# DE-160516.net
KiCad netlist of a schematic drawn in Altium Designer
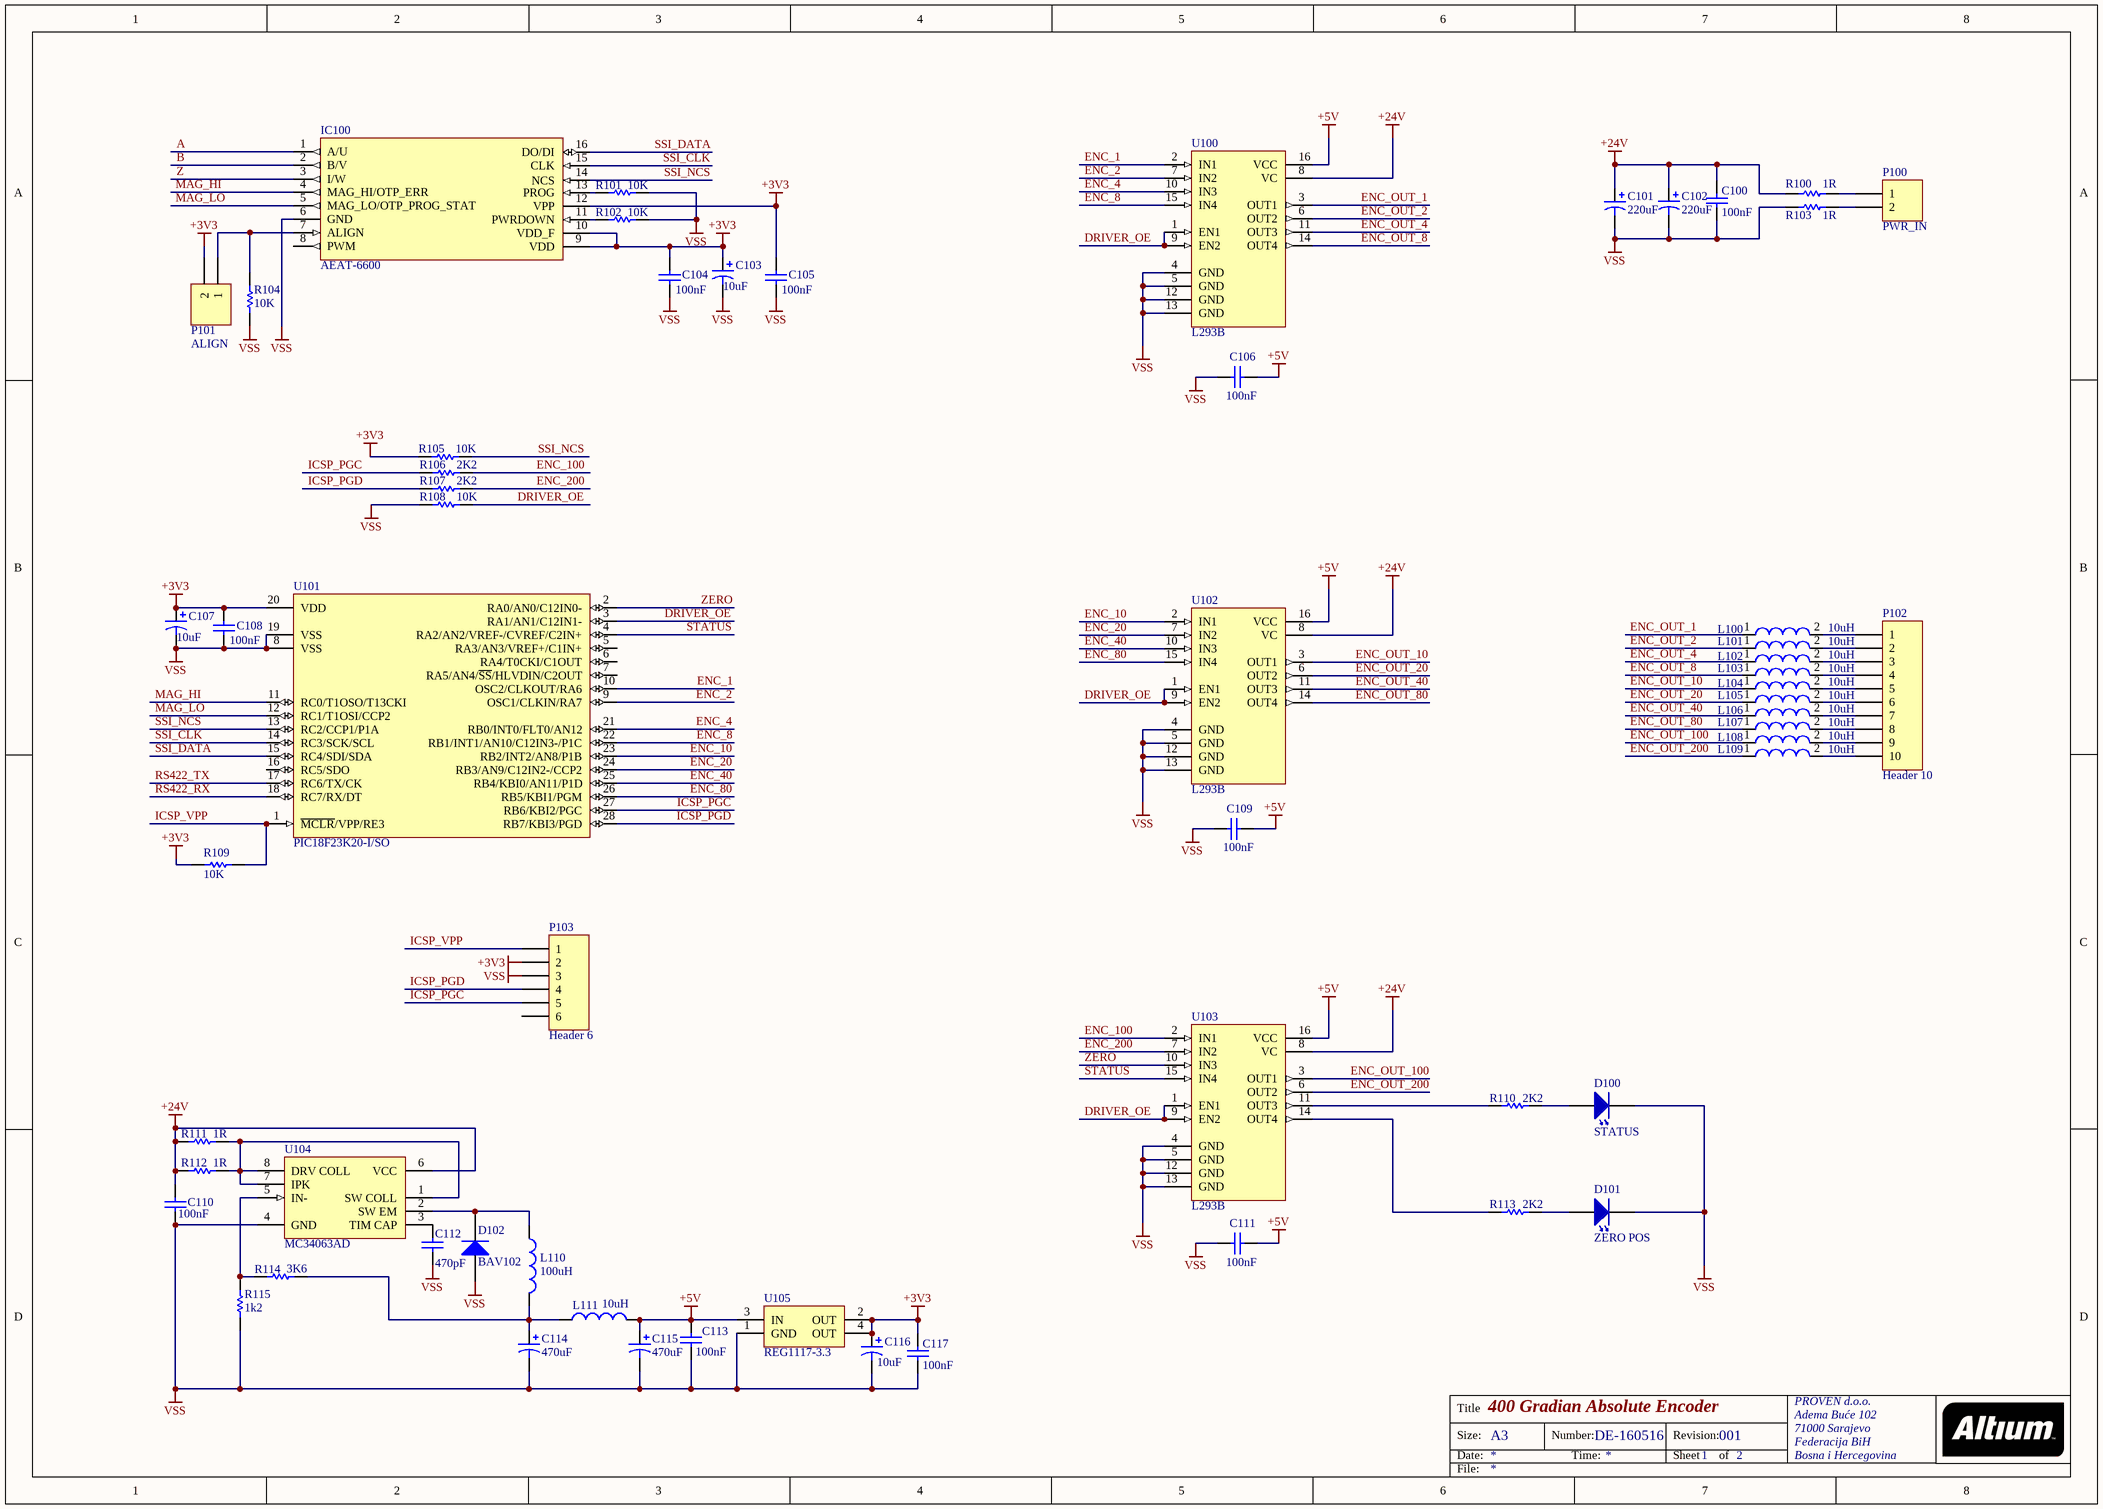
[diagram p0: DE-160516.SchDoc]

(export (version "E")
  (design (tool "Eeschema 10.0.6"))
  (components
    (comp (ref "C100")
      (value "100nF")
      (footprint "0805")
      (description "Ceramic Chip Capacitor - Standard")
      (fields (field (name "PUBLISHER") "Altium Limited"))
      (libsource (lib "KEMET Chip Capacitor") (part "C0805"))
    )
    (comp (ref "C101")
      (value "220uF")
      (footprint "E")
      (description "Solid Aluminum Capacitor with Organic Semiconductor Electrolyte: 100uF, 20V, Bulk Pack")
      (fields (field (name "PUBLISHER") "Altium Limited"))
      (libsource (lib "Vishay Electrolytic Radial-Lead Capacitor") (part "94SS107X0020EBP"))
    )
    (comp (ref "C102")
      (value "220uF")
      (footprint "E")
      (description "Solid Aluminum Capacitor with Organic Semiconductor Electrolyte: 100uF, 20V, Bulk Pack")
      (fields (field (name "PUBLISHER") "Altium Limited"))
      (libsource (lib "Vishay Electrolytic Radial-Lead Capacitor") (part "94SS107X0020EBP"))
    )
    (comp (ref "C103")
      (value "10uF")
      (footprint "C")
      (description "Solid Aluminum Capacitor with Organic Semiconductor Electrolyte: 10uF, 16V, Bulk Pack")
      (fields (field (name "PUBLISHER") "Altium Limited"))
      (libsource (lib "Vishay Electrolytic Radial-Lead Capacitor") (part "94SC106X0016CBP"))
    )
    (comp (ref "C104")
      (value "100nF")
      (footprint "0805")
      (description "Ceramic Chip Capacitor - Standard")
      (fields (field (name "PUBLISHER") "Altium Limited"))
      (libsource (lib "KEMET Chip Capacitor") (part "C0805"))
    )
    (comp (ref "C105")
      (value "100nF")
      (footprint "0805")
      (description "Ceramic Chip Capacitor - Standard")
      (fields (field (name "PUBLISHER") "Altium Limited"))
      (libsource (lib "KEMET Chip Capacitor") (part "C0805"))
    )
    (comp (ref "C106")
      (value "100nF")
      (footprint "0805")
      (description "Ceramic Chip Capacitor - Standard")
      (fields (field (name "PUBLISHER") "Altium Limited"))
      (libsource (lib "KEMET Chip Capacitor") (part "C0805"))
    )
    (comp (ref "C107")
      (value "10uF")
      (footprint "C")
      (description "Solid Aluminum Capacitor with Organic Semiconductor Electrolyte: 10uF, 16V, Bulk Pack")
      (fields (field (name "PUBLISHER") "Altium Limited"))
      (libsource (lib "Vishay Electrolytic Radial-Lead Capacitor") (part "94SC106X0016CBP"))
    )
    (comp (ref "C108")
      (value "100nF")
      (footprint "0805")
      (description "Ceramic Chip Capacitor - Standard")
      (fields (field (name "PUBLISHER") "Altium Limited"))
      (libsource (lib "KEMET Chip Capacitor") (part "C0805"))
    )
    (comp (ref "C109")
      (value "100nF")
      (footprint "0805")
      (description "Ceramic Chip Capacitor - Standard")
      (fields (field (name "PUBLISHER") "Altium Limited"))
      (libsource (lib "KEMET Chip Capacitor") (part "C0805"))
    )
    (comp (ref "C110")
      (value "100nF")
      (footprint "1206")
      (description "Ceramic Chip Capacitor - Standard")
      (fields (field (name "PUBLISHER") "Altium Limited"))
      (libsource (lib "KEMET Chip Capacitor") (part "C1206"))
    )
    (comp (ref "C111")
      (value "100nF")
      (footprint "0805")
      (description "Ceramic Chip Capacitor - Standard")
      (fields (field (name "PUBLISHER") "Altium Limited"))
      (libsource (lib "KEMET Chip Capacitor") (part "C0805"))
    )
    (comp (ref "C112")
      (value "470pF")
      (footprint "0805")
      (description "Ceramic Chip Capacitor - Standard")
      (fields (field (name "PUBLISHER") "Altium Limited"))
      (libsource (lib "KEMET Chip Capacitor") (part "C0805"))
    )
    (comp (ref "C113")
      (value "100nF")
      (footprint "0805")
      (description "Ceramic Chip Capacitor - Standard")
      (fields (field (name "PUBLISHER") "Altium Limited"))
      (libsource (lib "KEMET Chip Capacitor") (part "C0805"))
    )
    (comp (ref "C114")
      (value "470uF")
      (footprint "CAPPR2.5-6.3X11")
      (description "Aluminum Electrolytic Capacitor, Radial Style with Long Leads: 470uF, 10V")
      (fields (field (name "PUBLISHER") "Altium Limited"))
      (libsource (lib "Vishay Roederstein Electrolytic Radial-Lead Capacitor") (part "EKA00BA347C00"))
    )
    (comp (ref "C115")
      (value "470uF")
      (footprint "CAPPR2.5-6.3X11")
      (description "Aluminum Electrolytic Capacitor, Radial Style with Long Leads: 470uF, 10V")
      (fields (field (name "PUBLISHER") "Altium Limited"))
      (libsource (lib "Vishay Roederstein Electrolytic Radial-Lead Capacitor") (part "EKA00BA347C00"))
    )
    (comp (ref "C116")
      (value "10uF")
      (footprint "49BC-C")
      (fields (field (name "PUBLISHER") "Altium Limited"))
      (libsource (lib "Vishay Sprague Tantalum Chip Capacitor") (part "49BC685B010M"))
    )
    (comp (ref "C117")
      (value "100nF")
      (footprint "0805")
      (description "Ceramic Chip Capacitor - Standard")
      (fields (field (name "PUBLISHER") "Altium Limited"))
      (libsource (lib "KEMET Chip Capacitor") (part "C0805"))
    )
    (comp (ref "D100")
      (value "STATUS")
      (footprint "LED 3mm")
      (description "LED dioda 3 mm")
      (libsource (lib "Schlib1") (part "LED 3mm yellow"))
    )
    (comp (ref "D101")
      (value "ZERO POS")
      (footprint "LED 3mm")
      (description "LED dioda 3 mm")
      (libsource (lib "Schlib1") (part "LED 3mm yellow"))
    )
    (comp (ref "D102")
      (value "BAV102")
      (footprint "SOD80C")
      (description "General-purpose Diode")
      (fields (field (name "PUBLISHER") "Altium Limited"))
      (libsource (lib "Philips Discrete Diode - Switching") (part "BAV102"))
    )
    (comp (ref "IC100")
      (value "AEAT-6600")
      (footprint "TSSOP16")
      (description "Absolute encoder IC")
      (libsource (lib "ABS_ENC") (part "AEAT-6600"))
    )
    (comp (ref "L100")
      (value "10uH")
      (footprint "SMD-0603")
      (description "SMD-Multilayer Inductor WE-MI, L = 0.10µH")
      (libsource (lib "Wuerth Elektronik Filter Inductor") (part "7447962"))
    )
    (comp (ref "L101")
      (value "10uH")
      (footprint "SMD-0603")
      (description "SMD-Multilayer Inductor WE-MI, L = 0.10µH")
      (libsource (lib "Wuerth Elektronik Filter Inductor") (part "7447962"))
    )
    (comp (ref "L102")
      (value "10uH")
      (footprint "SMD-0603")
      (description "SMD-Multilayer Inductor WE-MI, L = 0.10µH")
      (libsource (lib "Wuerth Elektronik Filter Inductor") (part "7447962"))
    )
    (comp (ref "L103")
      (value "10uH")
      (footprint "SMD-0603")
      (description "SMD-Multilayer Inductor WE-MI, L = 0.10µH")
      (libsource (lib "Wuerth Elektronik Filter Inductor") (part "7447962"))
    )
    (comp (ref "L104")
      (value "10uH")
      (footprint "SMD-0603")
      (description "SMD-Multilayer Inductor WE-MI, L = 0.10µH")
      (libsource (lib "Wuerth Elektronik Filter Inductor") (part "7447962"))
    )
    (comp (ref "L105")
      (value "10uH")
      (footprint "SMD-0603")
      (description "SMD-Multilayer Inductor WE-MI, L = 0.10µH")
      (libsource (lib "Wuerth Elektronik Filter Inductor") (part "7447962"))
    )
    (comp (ref "L106")
      (value "10uH")
      (footprint "SMD-0603")
      (description "SMD-Multilayer Inductor WE-MI, L = 0.10µH")
      (libsource (lib "Wuerth Elektronik Filter Inductor") (part "7447962"))
    )
    (comp (ref "L107")
      (value "10uH")
      (footprint "SMD-0603")
      (description "SMD-Multilayer Inductor WE-MI, L = 0.10µH")
      (libsource (lib "Wuerth Elektronik Filter Inductor") (part "7447962"))
    )
    (comp (ref "L108")
      (value "10uH")
      (footprint "SMD-0603")
      (description "SMD-Multilayer Inductor WE-MI, L = 0.10µH")
      (libsource (lib "Wuerth Elektronik Filter Inductor") (part "7447962"))
    )
    (comp (ref "L109")
      (value "10uH")
      (footprint "SMD-0603")
      (description "SMD-Multilayer Inductor WE-MI, L = 0.10µH")
      (libsource (lib "Wuerth Elektronik Filter Inductor") (part "7447962"))
    )
    (comp (ref "L110")
      (value "100uH")
      (footprint "Miscellaneous Devices:RB5-10.5")
      (description "SMT Power Choke Coil; Size 7.3×6.6×3.0mm, ±20% Tolerance, 0.82uH, 13A")
      (fields (field (name "PUBLISHER") "Altium Limited"))
      (libsource (lib "SSM Inductor") (part "PCMC063T-R82MN"))
    )
    (comp (ref "L111")
      (value "10uH")
      (footprint "Miscellaneous Devices:RB5-10.5")
      (description "SMT Power Choke Coil; Size 7.3×6.6×3.0mm, ±20% Tolerance, 0.82uH, 13A")
      (fields (field (name "PUBLISHER") "Altium Limited"))
      (libsource (lib "SSM Inductor") (part "PCMC063T-R82MN"))
    )
    (comp (ref "P100")
      (value "PWR_IN")
      (footprint "HDR1X2")
      (description "Header, 2-Pin")
      (fields (field (name "PUBLISHER") "Altium Limited"))
      (libsource (lib "Miscellaneous Connectors") (part "Header 2"))
    )
    (comp (ref "P101")
      (value "ALIGN")
      (footprint "HDR1X2")
      (description "Header, 2-Pin")
      (fields (field (name "PUBLISHER") "Altium Limited"))
      (libsource (lib "") (part "Header 2_1"))
    )
    (comp (ref "P102")
      (value "Header 10")
      (footprint "HDR1X10")
      (description "Header, 10-Pin")
      (fields (field (name "PUBLISHER") "Altium Limited"))
      (libsource (lib "Miscellaneous Connectors") (part "Header 10"))
    )
    (comp (ref "P103")
      (value "Header 6")
      (footprint "HDR1X6")
      (description "Header, 6-Pin")
      (fields (field (name "PUBLISHER") "Altium Limited"))
      (libsource (lib "Miscellaneous Connectors") (part "Header 6"))
    )
    (comp (ref "R100")
      (value "1R")
      (footprint "RD6.35x2.3")
      (fields (field (name "PUBLISHER") "Altium Limited"))
      (libsource (lib "Panasonic Resistor") (part "ERD2FC"))
    )
    (comp (ref "R101")
      (value "10K")
      (footprint "ERA-0603")
      (fields (field (name "PUBLISHER") "Altium Limited"))
      (libsource (lib "Panasonic Resistor") (part "ERAV"))
    )
    (comp (ref "R102")
      (value "10K")
      (footprint "ERA-0603")
      (fields (field (name "PUBLISHER") "Altium Limited"))
      (libsource (lib "Panasonic Resistor") (part "ERAV"))
    )
    (comp (ref "R103")
      (value "1R")
      (footprint "RD6.35x2.3")
      (fields (field (name "PUBLISHER") "Altium Limited"))
      (libsource (lib "Panasonic Resistor") (part "ERD2FC"))
    )
    (comp (ref "R104")
      (value "10K")
      (footprint "ERA-0603")
      (fields (field (name "PUBLISHER") "Altium Limited"))
      (libsource (lib "Panasonic Resistor") (part "ERAV"))
    )
    (comp (ref "R105")
      (value "10K")
      (footprint "ERA-0603")
      (fields (field (name "PUBLISHER") "Altium Limited"))
      (libsource (lib "Panasonic Resistor") (part "ERAV"))
    )
    (comp (ref "R106")
      (value "2K2")
      (footprint "ERA-0603")
      (fields (field (name "PUBLISHER") "Altium Limited"))
      (libsource (lib "Panasonic Resistor") (part "ERAV"))
    )
    (comp (ref "R107")
      (value "2K2")
      (footprint "ERA-0603")
      (fields (field (name "PUBLISHER") "Altium Limited"))
      (libsource (lib "Panasonic Resistor") (part "ERAV"))
    )
    (comp (ref "R108")
      (value "10K")
      (footprint "ERA-0603")
      (fields (field (name "PUBLISHER") "Altium Limited"))
      (libsource (lib "Panasonic Resistor") (part "ERAV"))
    )
    (comp (ref "R109")
      (value "10K")
      (footprint "ERA-0603")
      (fields (field (name "PUBLISHER") "Altium Limited"))
      (libsource (lib "Panasonic Resistor") (part "ERAV"))
    )
    (comp (ref "R110")
      (value "2K2")
      (footprint "ERA-0603")
      (fields (field (name "PUBLISHER") "Altium Limited"))
      (libsource (lib "Panasonic Resistor") (part "ERAV"))
    )
    (comp (ref "R111")
      (value "1R")
      (footprint "ERA-0805")
      (fields (field (name "PUBLISHER") "Altium Limited"))
      (libsource (lib "Panasonic Resistor") (part "ERAS"))
    )
    (comp (ref "R112")
      (value "1R")
      (footprint "ERA-0805")
      (fields (field (name "PUBLISHER") "Altium Limited"))
      (libsource (lib "Panasonic Resistor") (part "ERAS"))
    )
    (comp (ref "R113")
      (value "2K2")
      (footprint "ERA-0603")
      (fields (field (name "PUBLISHER") "Altium Limited"))
      (libsource (lib "Panasonic Resistor") (part "ERAV"))
    )
    (comp (ref "R114")
      (value "3K6")
      (footprint "ERA-0805")
      (fields (field (name "PUBLISHER") "Altium Limited"))
      (libsource (lib "Panasonic Resistor") (part "ERAS"))
    )
    (comp (ref "R115")
      (value "1k2")
      (footprint "ERA-0805")
      (fields (field (name "PUBLISHER") "Altium Limited"))
      (libsource (lib "Panasonic Resistor") (part "ERAS"))
    )
    (comp (ref "U100")
      (value "L293B")
      (footprint "DIP16")
      (description "Push-Pull Four Channel Drivers")
      (fields (field (name "PUBLISHER") "Altium Limited"))
      (libsource (lib "ST Interface DC & Stepper Motor Controller") (part "L293B"))
    )
    (comp (ref "U101")
      (value "PIC18F23K20-I/SO")
      (footprint "SOIC-SO28_N")
      (description "Flash Microcontroller with nanoWatt XLP Technology, 28-pin SOIC, Industrial Temperature")
      (fields (field (name "PUBLISHER") "Altium Limited"))
      (libsource (lib "Microchip Microcontroller 8-Bit PIC18") (part "PIC18F23K20-I/SO"))
    )
    (comp (ref "U102")
      (value "L293B")
      (footprint "DIP16")
      (description "Push-Pull Four Channel Drivers")
      (fields (field (name "PUBLISHER") "Altium Limited"))
      (libsource (lib "ST Interface DC & Stepper Motor Controller") (part "L293B"))
    )
    (comp (ref "U103")
      (value "L293B")
      (footprint "DIP16")
      (description "Push-Pull Four Channel Drivers")
      (fields (field (name "PUBLISHER") "Altium Limited"))
      (libsource (lib "ST Interface DC & Stepper Motor Controller") (part "L293B"))
    )
    (comp (ref "U104")
      (value "MC34063AD")
      (footprint "751-05_N")
      (description "DC-to-DC Converter Control Circuit")
      (fields (field (name "PUBLISHER") "Altium Limited"))
      (libsource (lib "ON Semi Power Mgt DC-DC Converter") (part "MC34063AD"))
    )
    (comp (ref "U105")
      (value "REG1117-3.3")
      (footprint "ZZ311")
      (description "800mA and 1A Low Dropout Positive Regulator 2.85V, 3.3V, 5V, and Adjustable")
      (fields (field (name "PUBLISHER") "Altium Limited"))
      (libsource (lib "BB Power Mgt Voltage Regulator") (part "REG1117-3.3"))
    )
  )
  (nets
    (net (code "1") (name "+3V3") (class "Default")
      (node (ref "C103") (pin "1") (pinfunction "1_1") (pintype "passive"))
      (node (ref "C104") (pin "2") (pinfunction "2_2") (pintype "passive"))
      (node (ref "C105") (pin "2") (pinfunction "2_2") (pintype "passive"))
      (node (ref "C107") (pin "1") (pinfunction "1_1") (pintype "passive"))
      (node (ref "C108") (pin "2") (pinfunction "2_2") (pintype "passive"))
      (node (ref "C116") (pin "1") (pinfunction "1_1") (pintype "passive"))
      (node (ref "C117") (pin "2") (pinfunction "2_2") (pintype "passive"))
      (node (ref "IC100") (pin "10") (pinfunction "VDD_F_10") (pintype "power_in"))
      (node (ref "IC100") (pin "12") (pinfunction "VPP_12") (pintype "power_in"))
      (node (ref "IC100") (pin "9") (pinfunction "VDD_9") (pintype "power_in"))
      (node (ref "P101") (pin "2") (pinfunction "2_2") (pintype "passive"))
      (node (ref "P103") (pin "2") (pinfunction "2_2") (pintype "passive"))
      (node (ref "R105") (pin "2") (pinfunction "2_2") (pintype "passive"))
      (node (ref "R109") (pin "2") (pinfunction "2_2") (pintype "passive"))
      (node (ref "U101") (pin "20") (pinfunction "VDD_20") (pintype "power_in"))
      (node (ref "U105") (pin "2") (pinfunction "OUT_2") (pintype "power_in"))
      (node (ref "U105") (pin "4") (pinfunction "OUT_4") (pintype "power_in"))
    )
    (net (code "2") (name "+5V") (class "Default")
      (node (ref "C106") (pin "1") (pinfunction "1_1") (pintype "passive"))
      (node (ref "C109") (pin "1") (pinfunction "1_1") (pintype "passive"))
      (node (ref "C111") (pin "1") (pinfunction "1_1") (pintype "passive"))
      (node (ref "C113") (pin "2") (pinfunction "2_2") (pintype "passive"))
      (node (ref "C115") (pin "1") (pinfunction "1_1") (pintype "passive"))
      (node (ref "L111") (pin "2") (pinfunction "2_2") (pintype "passive"))
      (node (ref "U100") (pin "16") (pinfunction "VCC_16") (pintype "power_in"))
      (node (ref "U102") (pin "16") (pinfunction "VCC_16") (pintype "power_in"))
      (node (ref "U103") (pin "16") (pinfunction "VCC_16") (pintype "power_in"))
      (node (ref "U105") (pin "3") (pinfunction "IN_3") (pintype "power_in"))
    )
    (net (code "3") (name "+24V") (class "Default")
      (node (ref "C100") (pin "2") (pinfunction "2_2") (pintype "passive"))
      (node (ref "C101") (pin "1") (pinfunction "1_1") (pintype "passive"))
      (node (ref "C102") (pin "1") (pinfunction "1_1") (pintype "passive"))
      (node (ref "C110") (pin "2") (pinfunction "2_2") (pintype "passive"))
      (node (ref "R100") (pin "1") (pinfunction "1_1") (pintype "passive"))
      (node (ref "R111") (pin "1") (pinfunction "1_1") (pintype "passive"))
      (node (ref "R112") (pin "1") (pinfunction "1_1") (pintype "passive"))
      (node (ref "U100") (pin "8") (pinfunction "VC_8") (pintype "power_in"))
      (node (ref "U102") (pin "8") (pinfunction "VC_8") (pintype "power_in"))
      (node (ref "U103") (pin "8") (pinfunction "VC_8") (pintype "power_in"))
      (node (ref "U104") (pin "6") (pinfunction "VCC_6") (pintype "power_in"))
    )
    (net (code "4") (name "/A") (class "Default")
      (node (ref "IC100") (pin "1") (pinfunction "A/U_1") (pintype "output"))
    )
    (net (code "5") (name "/B") (class "Default")
      (node (ref "IC100") (pin "2") (pinfunction "B/V_2") (pintype "output"))
    )
    (net (code "6") (name "/DRIVER_OE") (class "Default")
      (node (ref "R108") (pin "1") (pinfunction "1_1") (pintype "passive"))
      (node (ref "U100") (pin "1") (pinfunction "EN1_1") (pintype "input"))
      (node (ref "U100") (pin "9") (pinfunction "EN2_9") (pintype "input"))
      (node (ref "U101") (pin "3") (pinfunction "RA1/AN1/C12IN1-_3") (pintype "bidirectional"))
      (node (ref "U102") (pin "1") (pinfunction "EN1_1") (pintype "input"))
      (node (ref "U102") (pin "9") (pinfunction "EN2_9") (pintype "input"))
      (node (ref "U103") (pin "1") (pinfunction "EN1_1") (pintype "input"))
      (node (ref "U103") (pin "9") (pinfunction "EN2_9") (pintype "input"))
    )
    (net (code "7") (name "/ENC_1") (class "Default")
      (node (ref "U100") (pin "2") (pinfunction "IN1_2") (pintype "input"))
      (node (ref "U101") (pin "10") (pinfunction "OSC2/CLKOUT/RA6_10") (pintype "bidirectional"))
    )
    (net (code "8") (name "/ENC_2") (class "Default")
      (node (ref "U100") (pin "7") (pinfunction "IN2_7") (pintype "input"))
      (node (ref "U101") (pin "9") (pinfunction "OSC1/CLKIN/RA7_9") (pintype "bidirectional"))
    )
    (net (code "9") (name "/ENC_4") (class "Default")
      (node (ref "U100") (pin "10") (pinfunction "IN3_10") (pintype "input"))
      (node (ref "U101") (pin "21") (pinfunction "RB0/INT0/FLT0/AN12_21") (pintype "bidirectional"))
    )
    (net (code "10") (name "/ENC_8") (class "Default")
      (node (ref "U100") (pin "15") (pinfunction "IN4_15") (pintype "input"))
      (node (ref "U101") (pin "22") (pinfunction "RB1/INT1/AN10/C12IN3-/P1C_22") (pintype "bidirectional"))
    )
    (net (code "11") (name "/ENC_10") (class "Default")
      (node (ref "U101") (pin "23") (pinfunction "RB2/INT2/AN8/P1B_23") (pintype "bidirectional"))
      (node (ref "U102") (pin "2") (pinfunction "IN1_2") (pintype "input"))
    )
    (net (code "12") (name "/ENC_20") (class "Default")
      (node (ref "U101") (pin "24") (pinfunction "RB3/AN9/C12IN2-/CCP2_24") (pintype "bidirectional"))
      (node (ref "U102") (pin "7") (pinfunction "IN2_7") (pintype "input"))
    )
    (net (code "13") (name "/ENC_40") (class "Default")
      (node (ref "U101") (pin "25") (pinfunction "RB4/KBI0/AN11/P1D_25") (pintype "bidirectional"))
      (node (ref "U102") (pin "10") (pinfunction "IN3_10") (pintype "input"))
    )
    (net (code "14") (name "/ENC_80") (class "Default")
      (node (ref "U101") (pin "26") (pinfunction "RB5/KBI1/PGM_26") (pintype "bidirectional"))
      (node (ref "U102") (pin "15") (pinfunction "IN4_15") (pintype "input"))
    )
    (net (code "15") (name "/ENC_100") (class "Default")
      (node (ref "R106") (pin "1") (pinfunction "1_1") (pintype "passive"))
      (node (ref "U103") (pin "2") (pinfunction "IN1_2") (pintype "input"))
    )
    (net (code "16") (name "/ENC_200") (class "Default")
      (node (ref "R107") (pin "1") (pinfunction "1_1") (pintype "passive"))
      (node (ref "U103") (pin "7") (pinfunction "IN2_7") (pintype "input"))
    )
    (net (code "17") (name "/ENC_OUT_1") (class "Default")
      (node (ref "L100") (pin "1") (pinfunction "1_1") (pintype "passive"))
      (node (ref "U100") (pin "3") (pinfunction "OUT1_3") (pintype "output"))
    )
    (net (code "18") (name "/ENC_OUT_2") (class "Default")
      (node (ref "L101") (pin "1") (pinfunction "1_1") (pintype "passive"))
      (node (ref "U100") (pin "6") (pinfunction "OUT2_6") (pintype "output"))
    )
    (net (code "19") (name "/ENC_OUT_4") (class "Default")
      (node (ref "L102") (pin "1") (pinfunction "1_1") (pintype "passive"))
      (node (ref "U100") (pin "11") (pinfunction "OUT3_11") (pintype "output"))
    )
    (net (code "20") (name "/ENC_OUT_8") (class "Default")
      (node (ref "L103") (pin "1") (pinfunction "1_1") (pintype "passive"))
      (node (ref "U100") (pin "14") (pinfunction "OUT4_14") (pintype "output"))
    )
    (net (code "21") (name "/ENC_OUT_10") (class "Default")
      (node (ref "L104") (pin "1") (pinfunction "1_1") (pintype "passive"))
      (node (ref "U102") (pin "3") (pinfunction "OUT1_3") (pintype "output"))
    )
    (net (code "22") (name "/ENC_OUT_20") (class "Default")
      (node (ref "L105") (pin "1") (pinfunction "1_1") (pintype "passive"))
      (node (ref "U102") (pin "6") (pinfunction "OUT2_6") (pintype "output"))
    )
    (net (code "23") (name "/ENC_OUT_40") (class "Default")
      (node (ref "L106") (pin "1") (pinfunction "1_1") (pintype "passive"))
      (node (ref "U102") (pin "11") (pinfunction "OUT3_11") (pintype "output"))
    )
    (net (code "24") (name "/ENC_OUT_80") (class "Default")
      (node (ref "L107") (pin "1") (pinfunction "1_1") (pintype "passive"))
      (node (ref "U102") (pin "14") (pinfunction "OUT4_14") (pintype "output"))
    )
    (net (code "25") (name "/ENC_OUT_100") (class "Default")
      (node (ref "L108") (pin "1") (pinfunction "1_1") (pintype "passive"))
      (node (ref "U103") (pin "3") (pinfunction "OUT1_3") (pintype "output"))
    )
    (net (code "26") (name "/ENC_OUT_200") (class "Default")
      (node (ref "L109") (pin "1") (pinfunction "1_1") (pintype "passive"))
      (node (ref "U103") (pin "6") (pinfunction "OUT2_6") (pintype "output"))
    )
    (net (code "27") (name "/ICSP_PGC") (class "Default")
      (node (ref "P103") (pin "5") (pinfunction "5_5") (pintype "passive"))
      (node (ref "R106") (pin "2") (pinfunction "2_2") (pintype "passive"))
      (node (ref "U101") (pin "27") (pinfunction "RB6/KBI2/PGC_27") (pintype "bidirectional"))
    )
    (net (code "28") (name "/ICSP_PGD") (class "Default")
      (node (ref "P103") (pin "4") (pinfunction "4_4") (pintype "passive"))
      (node (ref "R107") (pin "2") (pinfunction "2_2") (pintype "passive"))
      (node (ref "U101") (pin "28") (pinfunction "RB7/KBI3/PGD_28") (pintype "bidirectional"))
    )
    (net (code "29") (name "/ICSP_VPP") (class "Default")
      (node (ref "P103") (pin "1") (pinfunction "1_1") (pintype "passive"))
      (node (ref "R109") (pin "1") (pinfunction "1_1") (pintype "passive"))
      (node (ref "U101") (pin "1") (pinfunction "~{MCLR}/VPP/RE3_1") (pintype "input"))
    )
    (net (code "30") (name "/MAG_HI") (class "Default")
      (node (ref "IC100") (pin "4") (pinfunction "MAG_HI/OTP_ERR_4") (pintype "output"))
      (node (ref "U101") (pin "11") (pinfunction "RC0/T1OSO/T13CKI_11") (pintype "bidirectional"))
    )
    (net (code "31") (name "/MAG_LO") (class "Default")
      (node (ref "IC100") (pin "5") (pinfunction "MAG_LO/OTP_PROG_STAT_5") (pintype "output"))
      (node (ref "U101") (pin "12") (pinfunction "RC1/T1OSI/CCP2_12") (pintype "bidirectional"))
    )
    (net (code "32") (name "/RS422_RX") (class "Default")
      (node (ref "U101") (pin "18") (pinfunction "RC7/RX/DT_18") (pintype "bidirectional"))
    )
    (net (code "33") (name "/RS422_TX") (class "Default")
      (node (ref "U101") (pin "17") (pinfunction "RC6/TX/CK_17") (pintype "bidirectional"))
    )
    (net (code "34") (name "/SSI_CLK") (class "Default")
      (node (ref "IC100") (pin "15") (pinfunction "CLK_15") (pintype "input"))
      (node (ref "U101") (pin "14") (pinfunction "RC3/SCK/SCL_14") (pintype "bidirectional"))
    )
    (net (code "35") (name "/SSI_DATA") (class "Default")
      (node (ref "IC100") (pin "16") (pinfunction "DO/DI_16") (pintype "bidirectional"))
      (node (ref "U101") (pin "15") (pinfunction "RC4/SDI/SDA_15") (pintype "bidirectional"))
    )
    (net (code "36") (name "/SSI_NCS") (class "Default")
      (node (ref "IC100") (pin "14") (pinfunction "NCS_14") (pintype "input"))
      (node (ref "R105") (pin "1") (pinfunction "1_1") (pintype "passive"))
      (node (ref "U101") (pin "13") (pinfunction "RC2/CCP1/P1A_13") (pintype "bidirectional"))
    )
    (net (code "37") (name "/STATUS") (class "Default")
      (node (ref "U101") (pin "4") (pinfunction "RA2/AN2/VREF-/CVREF/C2IN+_4") (pintype "bidirectional"))
      (node (ref "U103") (pin "15") (pinfunction "IN4_15") (pintype "input"))
    )
    (net (code "38") (name "/Z") (class "Default")
      (node (ref "IC100") (pin "3") (pinfunction "I/W_3") (pintype "output"))
    )
    (net (code "39") (name "/ZERO") (class "Default")
      (node (ref "U101") (pin "2") (pinfunction "RA0/AN0/C12IN0-_2") (pintype "bidirectional"))
      (node (ref "U103") (pin "10") (pinfunction "IN3_10") (pintype "input"))
    )
    (net (code "40") (name "Net-(C114-Pad1)") (class "Default")
      (node (ref "C114") (pin "1") (pinfunction "1_1") (pintype "passive"))
      (node (ref "L110") (pin "2") (pinfunction "2_2") (pintype "passive"))
      (node (ref "L111") (pin "1") (pinfunction "1_1") (pintype "passive"))
      (node (ref "R114") (pin "2") (pinfunction "2_2") (pintype "passive"))
    )
    (net (code "41") (name "Net-(D100-Pad2)") (class "Default")
      (node (ref "D100") (pin "2") (pinfunction "2_2") (pintype "passive"))
      (node (ref "R110") (pin "2") (pinfunction "2_2") (pintype "passive"))
    )
    (net (code "42") (name "Net-(D101-Pad2)") (class "Default")
      (node (ref "D101") (pin "2") (pinfunction "2_2") (pintype "passive"))
      (node (ref "R113") (pin "2") (pinfunction "2_2") (pintype "passive"))
    )
    (net (code "43") (name "Net-(D102-K)") (class "Default")
      (node (ref "D102") (pin "2") (pinfunction "K_2") (pintype "passive"))
      (node (ref "L110") (pin "1") (pinfunction "1_1") (pintype "passive"))
      (node (ref "U104") (pin "2") (pinfunction "SW_EM_2") (pintype "passive"))
    )
    (net (code "44") (name "Net-(IC100-ALIGN)") (class "Default")
      (node (ref "IC100") (pin "7") (pinfunction "ALIGN_7") (pintype "input"))
      (node (ref "P101") (pin "1") (pinfunction "1_1") (pintype "passive"))
      (node (ref "R104") (pin "2") (pinfunction "2_2") (pintype "passive"))
    )
    (net (code "45") (name "Net-(IC100-PROG)") (class "Default")
      (node (ref "IC100") (pin "13") (pinfunction "PROG_13") (pintype "input"))
      (node (ref "R101") (pin "2") (pinfunction "2_2") (pintype "passive"))
    )
    (net (code "46") (name "Net-(IC100-PWRDOWN)") (class "Default")
      (node (ref "IC100") (pin "11") (pinfunction "PWRDOWN_11") (pintype "input"))
      (node (ref "R102") (pin "2") (pinfunction "2_2") (pintype "passive"))
    )
    (net (code "47") (name "Net-(L100-Pad2)") (class "Default")
      (node (ref "L100") (pin "2") (pinfunction "2_2") (pintype "passive"))
      (node (ref "P102") (pin "1") (pinfunction "1_1") (pintype "passive"))
    )
    (net (code "48") (name "Net-(L101-Pad2)") (class "Default")
      (node (ref "L101") (pin "2") (pinfunction "2_2") (pintype "passive"))
      (node (ref "P102") (pin "2") (pinfunction "2_2") (pintype "passive"))
    )
    (net (code "49") (name "Net-(L102-Pad2)") (class "Default")
      (node (ref "L102") (pin "2") (pinfunction "2_2") (pintype "passive"))
      (node (ref "P102") (pin "3") (pinfunction "3_3") (pintype "passive"))
    )
    (net (code "50") (name "Net-(L103-Pad2)") (class "Default")
      (node (ref "L103") (pin "2") (pinfunction "2_2") (pintype "passive"))
      (node (ref "P102") (pin "4") (pinfunction "4_4") (pintype "passive"))
    )
    (net (code "51") (name "Net-(L104-Pad2)") (class "Default")
      (node (ref "L104") (pin "2") (pinfunction "2_2") (pintype "passive"))
      (node (ref "P102") (pin "5") (pinfunction "5_5") (pintype "passive"))
    )
    (net (code "52") (name "Net-(L105-Pad2)") (class "Default")
      (node (ref "L105") (pin "2") (pinfunction "2_2") (pintype "passive"))
      (node (ref "P102") (pin "6") (pinfunction "6_6") (pintype "passive"))
    )
    (net (code "53") (name "Net-(L106-Pad2)") (class "Default")
      (node (ref "L106") (pin "2") (pinfunction "2_2") (pintype "passive"))
      (node (ref "P102") (pin "7") (pinfunction "7_7") (pintype "passive"))
    )
    (net (code "54") (name "Net-(L107-Pad2)") (class "Default")
      (node (ref "L107") (pin "2") (pinfunction "2_2") (pintype "passive"))
      (node (ref "P102") (pin "8") (pinfunction "8_8") (pintype "passive"))
    )
    (net (code "55") (name "Net-(L108-Pad2)") (class "Default")
      (node (ref "L108") (pin "2") (pinfunction "2_2") (pintype "passive"))
      (node (ref "P102") (pin "9") (pinfunction "9_9") (pintype "passive"))
    )
    (net (code "56") (name "Net-(L109-Pad2)") (class "Default")
      (node (ref "L109") (pin "2") (pinfunction "2_2") (pintype "passive"))
      (node (ref "P102") (pin "10") (pinfunction "10_10") (pintype "passive"))
    )
    (net (code "57") (name "Net-(P100-Pad1)") (class "Default")
      (node (ref "P100") (pin "1") (pinfunction "1_1") (pintype "passive"))
      (node (ref "R100") (pin "2") (pinfunction "2_2") (pintype "passive"))
    )
    (net (code "58") (name "Net-(P100-Pad2)") (class "Default")
      (node (ref "P100") (pin "2") (pinfunction "2_2") (pintype "passive"))
      (node (ref "R103") (pin "2") (pinfunction "2_2") (pintype "passive"))
    )
    (net (code "59") (name "Net-(U103-OUT3)") (class "Default")
      (node (ref "R110") (pin "1") (pinfunction "1_1") (pintype "passive"))
      (node (ref "U103") (pin "11") (pinfunction "OUT3_11") (pintype "output"))
    )
    (net (code "60") (name "Net-(U103-OUT4)") (class "Default")
      (node (ref "R113") (pin "1") (pinfunction "1_1") (pintype "passive"))
      (node (ref "U103") (pin "14") (pinfunction "OUT4_14") (pintype "output"))
    )
    (net (code "61") (name "Net-(U104-DRV_COLL)") (class "Default")
      (node (ref "R111") (pin "2") (pinfunction "2_2") (pintype "passive"))
      (node (ref "R112") (pin "2") (pinfunction "2_2") (pintype "passive"))
      (node (ref "U104") (pin "1") (pinfunction "SW_COLL_1") (pintype "passive"))
      (node (ref "U104") (pin "7") (pinfunction "IPK_7") (pintype "passive"))
      (node (ref "U104") (pin "8") (pinfunction "DRV_COLL_8") (pintype "open_collector"))
    )
    (net (code "62") (name "Net-(U104-IN-)") (class "Default")
      (node (ref "R114") (pin "1") (pinfunction "1_1") (pintype "passive"))
      (node (ref "R115") (pin "2") (pinfunction "2_2") (pintype "passive"))
      (node (ref "U104") (pin "5") (pinfunction "IN-_5") (pintype "input"))
    )
    (net (code "63") (name "Net-(U104-TIM_CAP)") (class "Default")
      (node (ref "C112") (pin "2") (pinfunction "2_2") (pintype "passive"))
      (node (ref "U104") (pin "3") (pinfunction "TIM_CAP_3") (pintype "passive"))
    )
    (net (code "64") (name "VSS") (class "Default")
      (node (ref "C100") (pin "1") (pinfunction "1_1") (pintype "passive"))
      (node (ref "C101") (pin "2") (pinfunction "2_2") (pintype "passive"))
      (node (ref "C102") (pin "2") (pinfunction "2_2") (pintype "passive"))
      (node (ref "C103") (pin "2") (pinfunction "2_2") (pintype "passive"))
      (node (ref "C104") (pin "1") (pinfunction "1_1") (pintype "passive"))
      (node (ref "C105") (pin "1") (pinfunction "1_1") (pintype "passive"))
      (node (ref "C106") (pin "2") (pinfunction "2_2") (pintype "passive"))
      (node (ref "C107") (pin "2") (pinfunction "2_2") (pintype "passive"))
      (node (ref "C108") (pin "1") (pinfunction "1_1") (pintype "passive"))
      (node (ref "C109") (pin "2") (pinfunction "2_2") (pintype "passive"))
      (node (ref "C110") (pin "1") (pinfunction "1_1") (pintype "passive"))
      (node (ref "C111") (pin "2") (pinfunction "2_2") (pintype "passive"))
      (node (ref "C112") (pin "1") (pinfunction "1_1") (pintype "passive"))
      (node (ref "C113") (pin "1") (pinfunction "1_1") (pintype "passive"))
      (node (ref "C114") (pin "2") (pinfunction "2_2") (pintype "passive"))
      (node (ref "C115") (pin "2") (pinfunction "2_2") (pintype "passive"))
      (node (ref "C116") (pin "2") (pinfunction "2_2") (pintype "passive"))
      (node (ref "C117") (pin "1") (pinfunction "1_1") (pintype "passive"))
      (node (ref "D100") (pin "1") (pinfunction "1_1") (pintype "passive"))
      (node (ref "D101") (pin "1") (pinfunction "1_1") (pintype "passive"))
      (node (ref "D102") (pin "1") (pinfunction "A_1") (pintype "passive"))
      (node (ref "IC100") (pin "6") (pinfunction "GND_6") (pintype "power_in"))
      (node (ref "P103") (pin "3") (pinfunction "3_3") (pintype "passive"))
      (node (ref "R101") (pin "1") (pinfunction "1_1") (pintype "passive"))
      (node (ref "R102") (pin "1") (pinfunction "1_1") (pintype "passive"))
      (node (ref "R103") (pin "1") (pinfunction "1_1") (pintype "passive"))
      (node (ref "R104") (pin "1") (pinfunction "1_1") (pintype "passive"))
      (node (ref "R108") (pin "2") (pinfunction "2_2") (pintype "passive"))
      (node (ref "R115") (pin "1") (pinfunction "1_1") (pintype "passive"))
      (node (ref "U100") (pin "12") (pinfunction "GND_12") (pintype "power_in"))
      (node (ref "U100") (pin "13") (pinfunction "GND_13") (pintype "power_in"))
      (node (ref "U100") (pin "4") (pinfunction "GND_4") (pintype "power_in"))
      (node (ref "U100") (pin "5") (pinfunction "GND_5") (pintype "power_in"))
      (node (ref "U101") (pin "19") (pinfunction "VSS_19") (pintype "power_in"))
      (node (ref "U101") (pin "8") (pinfunction "VSS_8") (pintype "power_in"))
      (node (ref "U102") (pin "12") (pinfunction "GND_12") (pintype "power_in"))
      (node (ref "U102") (pin "13") (pinfunction "GND_13") (pintype "power_in"))
      (node (ref "U102") (pin "4") (pinfunction "GND_4") (pintype "power_in"))
      (node (ref "U102") (pin "5") (pinfunction "GND_5") (pintype "power_in"))
      (node (ref "U103") (pin "12") (pinfunction "GND_12") (pintype "power_in"))
      (node (ref "U103") (pin "13") (pinfunction "GND_13") (pintype "power_in"))
      (node (ref "U103") (pin "4") (pinfunction "GND_4") (pintype "power_in"))
      (node (ref "U103") (pin "5") (pinfunction "GND_5") (pintype "power_in"))
      (node (ref "U104") (pin "4") (pinfunction "GND_4") (pintype "power_in"))
      (node (ref "U105") (pin "1") (pinfunction "GND_1") (pintype "power_in"))
    )
    (net (code "65") (name "unconnected-(IC100-PWM-Pad8)") (class "Default")
      (node (ref "IC100") (pin "8") (pinfunction "PWM_8") (pintype "output"))
    )
    (net (code "66") (name "unconnected-(P103-Pad6)") (class "Default")
      (node (ref "P103") (pin "6") (pinfunction "6_6") (pintype "passive"))
    )
    (net (code "67") (name "unconnected-(U101-RA3{slash}AN3{slash}VREF+{slash}C1IN+-Pad5)") (class "Default")
      (node (ref "U101") (pin "5") (pinfunction "RA3/AN3/VREF+/C1IN+_5") (pintype "bidirectional"))
    )
    (net (code "68") (name "unconnected-(U101-RA4{slash}T0CKI{slash}C1OUT-Pad6)") (class "Default")
      (node (ref "U101") (pin "6") (pinfunction "RA4/T0CKI/C1OUT_6") (pintype "bidirectional"))
    )
    (net (code "69") (name "unconnected-(U101-RA5{slash}AN4{slash}~{SS}{slash}HLVDIN{slash}C2OUT-Pad7)") (class "Default")
      (node (ref "U101") (pin "7") (pinfunction "RA5/AN4/~{SS}/HLVDIN/C2OUT_7") (pintype "bidirectional"))
    )
    (net (code "70") (name "unconnected-(U101-RC5{slash}SDO-Pad16)") (class "Default")
      (node (ref "U101") (pin "16") (pinfunction "RC5/SDO_16") (pintype "bidirectional"))
    )
  )
)
